# st-link.net
KiCad netlist of a schematic drawn in Altium Designer
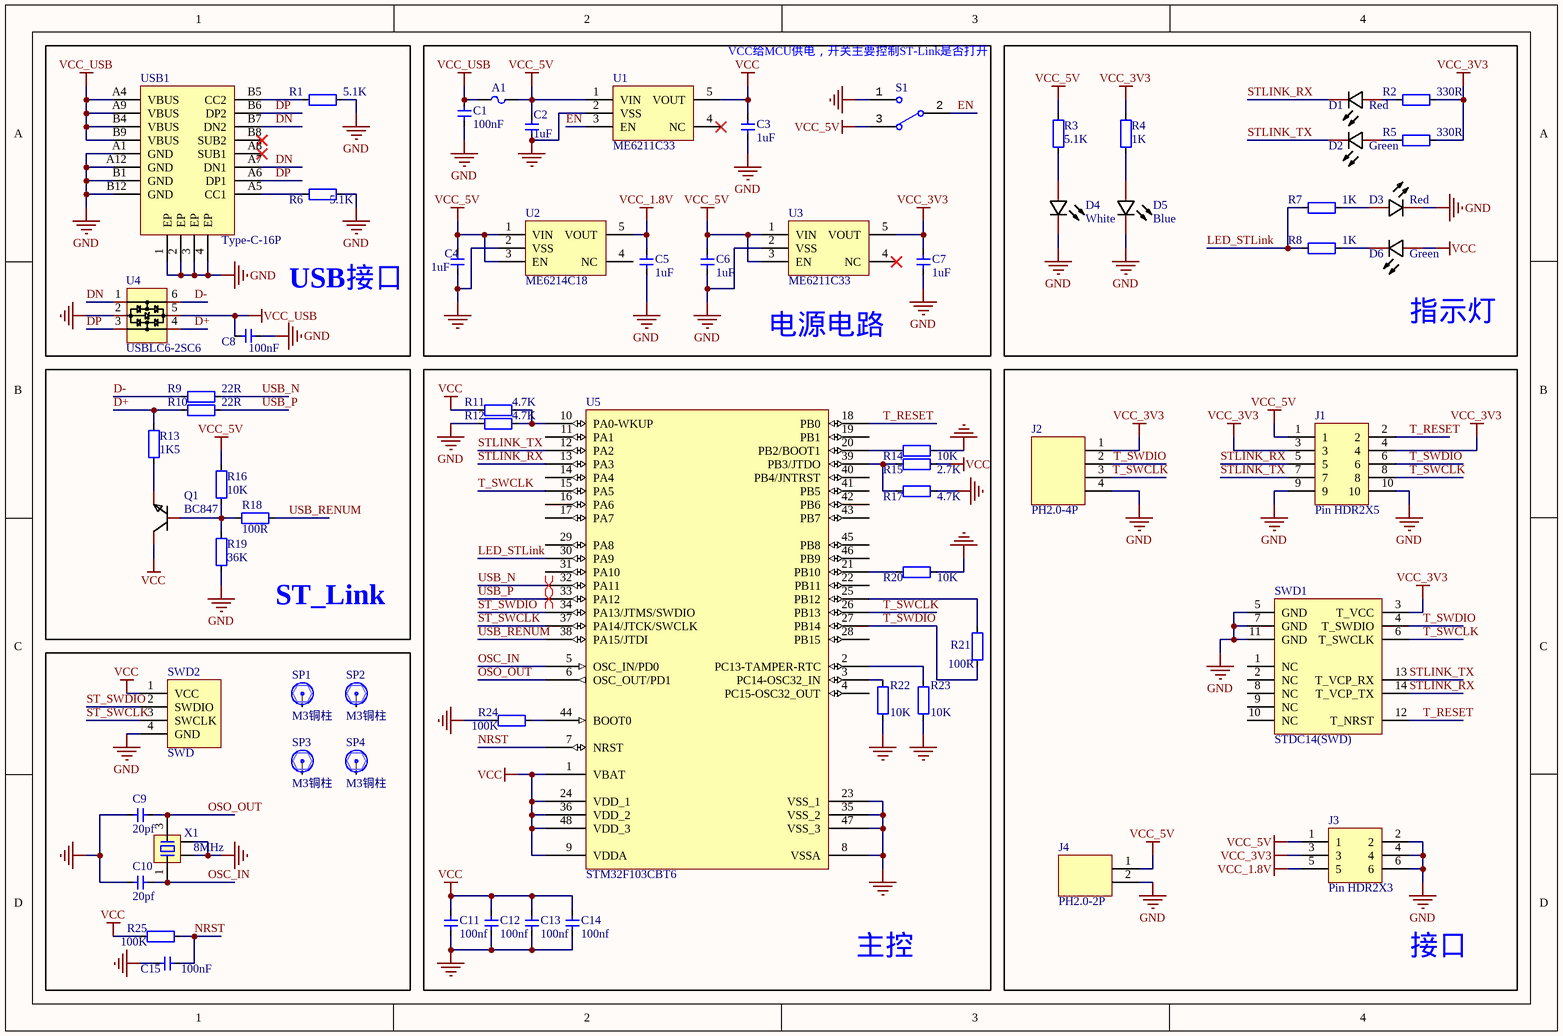
[diagram p0: st-link.SchDoc]

(export (version "E")
  (design (tool "Eeschema 10.0.6"))
  (components
    (comp (ref "A1")
      (value "ASMD1812-300")
      (footprint "FUSE-1812")
      (libsource (lib "xiaomo") (part "ASMD1812-300"))
    )
    (comp (ref "C1")
      (value "100nF")
      (footprint "CAP_0402")
      (description "Capacitor")
      (libsource (lib "xiaomo") (part "电容-0402"))
    )
    (comp (ref "C2")
      (value "1uF")
      (footprint "CAP_0402")
      (description "Capacitor")
      (libsource (lib "xiaomo") (part "电容-0402"))
    )
    (comp (ref "C3")
      (value "1uF")
      (footprint "CAP_0402")
      (description "Capacitor")
      (libsource (lib "xiaomo") (part "电容-0402"))
    )
    (comp (ref "C4")
      (value "1uF")
      (footprint "CAP_0402")
      (description "Capacitor")
      (libsource (lib "xiaomo") (part "电容-0402"))
    )
    (comp (ref "C5")
      (value "1uF")
      (footprint "CAP_0402")
      (description "Capacitor")
      (libsource (lib "xiaomo") (part "电容-0402"))
    )
    (comp (ref "C6")
      (value "1uF")
      (footprint "CAP_0402")
      (description "Capacitor")
      (libsource (lib "xiaomo") (part "电容-0402"))
    )
    (comp (ref "C7")
      (value "1uF")
      (footprint "CAP_0402")
      (description "Capacitor")
      (libsource (lib "xiaomo") (part "电容-0402"))
    )
    (comp (ref "C8")
      (value "100nF")
      (footprint "CAP_0402")
      (description "Capacitor")
      (libsource (lib "xiaomo") (part "电容-0402"))
    )
    (comp (ref "C9")
      (value "20pf")
      (footprint "CAP_0402")
      (description "Capacitor")
      (libsource (lib "xiaomo") (part "电容-0402"))
    )
    (comp (ref "C10")
      (value "20pf")
      (footprint "CAP_0402")
      (description "Capacitor")
      (libsource (lib "xiaomo") (part "电容-0402"))
    )
    (comp (ref "C11")
      (value "100nf")
      (footprint "CAP_0402")
      (description "Capacitor")
      (libsource (lib "xiaomo") (part "电容-0402"))
    )
    (comp (ref "C12")
      (value "100nf")
      (footprint "CAP_0402")
      (description "Capacitor")
      (libsource (lib "xiaomo") (part "电容-0402"))
    )
    (comp (ref "C13")
      (value "100nf")
      (footprint "CAP_0402")
      (description "Capacitor")
      (libsource (lib "xiaomo") (part "电容-0402"))
    )
    (comp (ref "C14")
      (value "100nf")
      (footprint "CAP_0402")
      (description "Capacitor")
      (libsource (lib "xiaomo") (part "电容-0402"))
    )
    (comp (ref "C15")
      (value "100nF")
      (footprint "CAP_0402")
      (description "Capacitor")
      (libsource (lib "xiaomo") (part "电容-0402"))
    )
    (comp (ref "D1")
      (value "Red")
      (footprint "LED-0603G")
      (description "0603LED")
      (libsource (lib "xiaomo") (part "LED0603"))
    )
    (comp (ref "D2")
      (value "Green")
      (footprint "LED-0603G")
      (description "0603LED")
      (libsource (lib "xiaomo") (part "LED0603"))
    )
    (comp (ref "D3")
      (value "Red")
      (footprint "LED-0603G")
      (description "0603LED")
      (libsource (lib "xiaomo") (part "LED0603"))
    )
    (comp (ref "D4")
      (value "White")
      (footprint "LED-0603G")
      (description "0603LED")
      (libsource (lib "xiaomo") (part "LED0603"))
    )
    (comp (ref "D5")
      (value "Blue")
      (footprint "LED-0603G")
      (description "0603LED")
      (libsource (lib "xiaomo") (part "LED0603"))
    )
    (comp (ref "D6")
      (value "Green")
      (footprint "LED-0603G")
      (description "0603LED")
      (libsource (lib "xiaomo") (part "LED0603"))
    )
    (comp (ref "J1")
      (value "Pin HDR2X5")
      (footprint "Pin HDR2X5/2.54mm-S")
      (libsource (lib "排针") (part "Pin HDR2X5"))
    )
    (comp (ref "J2") (value "PH2.0-4P") (footprint "PH2.0-4P") (libsource (lib "PH") (part "PH2.0-4P")))
    (comp (ref "J3")
      (value "Pin HDR2X3")
      (footprint "Pin HDR2X3/2.54mm-S")
      (libsource (lib "排针") (part "Pin HDR2X3"))
    )
    (comp (ref "J4") (value "PH2.0-2P") (footprint "PH2.0-2P") (libsource (lib "PH") (part "PH2.0-2P")))
    (comp (ref "Q1") (value "BC847") (footprint "SOT23-3") (libsource (lib "xiaomo") (part "NPN")))
    (comp (ref "R1")
      (value "5.1K")
      (footprint "RES_0402")
      (description "Resistor")
      (libsource (lib "") (part "电阻-0402_2"))
    )
    (comp (ref "R2")
      (value "330R")
      (footprint "RES_0402")
      (description "Resistor")
      (libsource (lib "") (part "电阻-0402_2"))
    )
    (comp (ref "R3")
      (value "5.1K")
      (footprint "RES_0402")
      (description "Resistor")
      (libsource (lib "") (part "电阻-0402_1"))
    )
    (comp (ref "R4")
      (value "1K")
      (footprint "RES_0402")
      (description "Resistor")
      (libsource (lib "") (part "电阻-0402_1"))
    )
    (comp (ref "R5")
      (value "330R")
      (footprint "RES_0402")
      (description "Resistor")
      (libsource (lib "") (part "电阻-0402_2"))
    )
    (comp (ref "R6")
      (value "5.1K")
      (footprint "RES_0402")
      (description "Resistor")
      (libsource (lib "") (part "电阻-0402_2"))
    )
    (comp (ref "R7")
      (value "1K")
      (footprint "RES_0402")
      (description "Resistor")
      (libsource (lib "") (part "电阻-0402_2"))
    )
    (comp (ref "R8")
      (value "1K")
      (footprint "RES_0402")
      (description "Resistor")
      (libsource (lib "") (part "电阻-0402_2"))
    )
    (comp (ref "R9")
      (value "22R")
      (footprint "RES_0402")
      (description "Resistor")
      (libsource (lib "") (part "电阻-0402_2"))
    )
    (comp (ref "R10")
      (value "22R")
      (footprint "RES_0402")
      (description "Resistor")
      (libsource (lib "") (part "电阻-0402_2"))
    )
    (comp (ref "R11")
      (value "4.7K")
      (footprint "RES_0402")
      (description "Resistor")
      (libsource (lib "") (part "电阻-0402_3"))
    )
    (comp (ref "R12")
      (value "4.7K")
      (footprint "RES_0402")
      (description "Resistor")
      (libsource (lib "") (part "电阻-0402_3"))
    )
    (comp (ref "R13")
      (value "1K5")
      (footprint "RES_0402")
      (description "Resistor")
      (libsource (lib "xiaomo") (part "电阻-0402"))
    )
    (comp (ref "R14")
      (value "10K")
      (footprint "RES_0402")
      (description "Resistor")
      (libsource (lib "") (part "电阻-0402_2"))
    )
    (comp (ref "R15")
      (value "2.7K")
      (footprint "RES_0402")
      (description "Resistor")
      (libsource (lib "") (part "电阻-0402_2"))
    )
    (comp (ref "R16")
      (value "10K")
      (footprint "RES_0402")
      (description "Resistor")
      (libsource (lib "xiaomo") (part "电阻-0402"))
    )
    (comp (ref "R17")
      (value "4.7K")
      (footprint "RES_0402")
      (description "Resistor")
      (libsource (lib "") (part "电阻-0402_2"))
    )
    (comp (ref "R18")
      (value "100R")
      (footprint "RES_0402")
      (description "Resistor")
      (libsource (lib "") (part "电阻-0402_2"))
    )
    (comp (ref "R19")
      (value "36K")
      (footprint "RES_0402")
      (description "Resistor")
      (libsource (lib "xiaomo") (part "电阻-0402"))
    )
    (comp (ref "R20")
      (value "10K")
      (footprint "RES_0402")
      (description "Resistor")
      (libsource (lib "") (part "电阻-0402_2"))
    )
    (comp (ref "R21")
      (value "100R")
      (footprint "RES_0402")
      (description "Resistor")
      (libsource (lib "") (part "电阻-0402_1"))
    )
    (comp (ref "R22")
      (value "10K")
      (footprint "RES_0402")
      (description "Resistor")
      (libsource (lib "") (part "电阻-0402_1"))
    )
    (comp (ref "R23")
      (value "10K")
      (footprint "RES_0402")
      (description "Resistor")
      (libsource (lib "") (part "电阻-0402_1"))
    )
    (comp (ref "R24")
      (value "100K")
      (footprint "RES_0402")
      (description "Resistor")
      (libsource (lib "") (part "电阻-0402_3"))
    )
    (comp (ref "R25")
      (value "100K")
      (footprint "RES_0402")
      (description "Resistor")
      (libsource (lib "") (part "电阻-0402_3"))
    )
    (comp (ref "S1")
      (value "SPDT 3P")
      (footprint "SwitchSPDT_2.8X6.6_90")
      (description "Switch")
      (libsource (lib "xiaomo") (part "SwitchSPDT_2.8x6.6_90"))
    )
    (comp (ref "SP1")
      (value "M3铜柱")
      (footprint "铜柱")
      (description "铜柱")
      (fields (field (name "版权归属") "源创客"))
      (libsource (lib "固定柱") (part "铜柱"))
    )
    (comp (ref "SP2")
      (value "M3铜柱")
      (footprint "铜柱")
      (description "铜柱")
      (fields (field (name "版权归属") "源创客"))
      (libsource (lib "固定柱") (part "铜柱"))
    )
    (comp (ref "SP3")
      (value "M3铜柱")
      (footprint "铜柱")
      (description "铜柱")
      (fields (field (name "版权归属") "源创客"))
      (libsource (lib "固定柱") (part "铜柱"))
    )
    (comp (ref "SP4")
      (value "M3铜柱")
      (footprint "铜柱")
      (description "铜柱")
      (fields (field (name "版权归属") "源创客"))
      (libsource (lib "固定柱") (part "铜柱"))
    )
    (comp (ref "SWD1")
      (value "STDC14(SWD)")
      (footprint "STDC14")
      (description "For STLINK_V3SET")
      (libsource (lib "xiaomo") (part "STDC14(SWD)"))
    )
    (comp (ref "SWD2") (value "SWD") (footprint "焊点×4") (libsource (lib "xiaomo") (part "SWD")))
    (comp (ref "U1")
      (value "ME6211C33")
      (footprint "SOT23-5")
      (description "低压差线性稳压器")
      (libsource (lib "xiaomo") (part "ME6211C"))
    )
    (comp (ref "U2")
      (value "ME6214C18")
      (footprint "SOT23-5")
      (description "低压差线性稳压器")
      (libsource (lib "xiaomo") (part "ME6211C"))
    )
    (comp (ref "U3")
      (value "ME6211C33")
      (footprint "SOT23-5")
      (description "低压差线性稳压器")
      (libsource (lib "xiaomo") (part "ME6211C"))
    )
    (comp (ref "U4")
      (value "USBLC6-2SC6")
      (footprint "SOT23-6")
      (description "静电放电(ESD)保护器件，反向截止电压(Vrwm)：5.25V 击穿电压：6V 峰值脉冲电流(Ipp)：5A@8/20us 最大钳位电压(Vc)@Ipp：17V")
      (libsource (lib "xiaomo") (part "USBLC6-2SC6"))
    )
    (comp (ref "U5")
      (value "STM32F103CBT6")
      (footprint "LQFP48 7X7")
      (libsource (lib "STM32系列") (part "STM32F103C8T6"))
    )
    (comp (ref "USB1")
      (value "Type-C-16P")
      (footprint "USB-C-SMD_KH-TYPE-C-16P")
      (description "C709357")
      (libsource (lib "xiaomo") (part "Type-C-16P"))
    )
    (comp (ref "X1")
      (value "8MHz")
      (footprint "OSC 3225-4P")
      (description "4脚无源晶振")
      (libsource (lib "晶振") (part "XTAL-4P"))
    )
  )
  (nets
    (net (code "1") (name "/D+") (class "Default")
      (node (ref "R10") (pin "1") (pinfunction "1_1") (pintype "passive"))
      (node (ref "R13") (pin "2") (pinfunction "2_2") (pintype "passive"))
      (node (ref "U4") (pin "4") (pinfunction "I/O2_4") (pintype "passive"))
    )
    (net (code "2") (name "/D-") (class "Default")
      (node (ref "R9") (pin "1") (pinfunction "1_1") (pintype "passive"))
      (node (ref "U4") (pin "6") (pinfunction "I/O1_6") (pintype "passive"))
    )
    (net (code "3") (name "/DN") (class "Default")
      (node (ref "U4") (pin "1") (pinfunction "I/O1_1") (pintype "passive"))
      (node (ref "USB1") (pin "A7") (pinfunction "DN1_A7") (pintype "passive"))
      (node (ref "USB1") (pin "B7") (pinfunction "DN2_B7") (pintype "passive"))
    )
    (net (code "4") (name "/DP") (class "Default")
      (node (ref "U4") (pin "3") (pinfunction "I/O2_3") (pintype "passive"))
      (node (ref "USB1") (pin "A6") (pinfunction "DP1_A6") (pintype "passive"))
      (node (ref "USB1") (pin "B6") (pinfunction "DP2_B6") (pintype "passive"))
    )
    (net (code "5") (name "/EN") (class "Default")
      (node (ref "S1") (pin "2") (pinfunction "2_2") (pintype "passive"))
      (node (ref "U1") (pin "3") (pinfunction "EN_3") (pintype "passive"))
    )
    (net (code "6") (name "/LED_STLink") (class "Default")
      (node (ref "R7") (pin "1") (pinfunction "1_1") (pintype "passive"))
      (node (ref "R8") (pin "1") (pinfunction "1_1") (pintype "passive"))
      (node (ref "U5") (pin "30") (pinfunction "PA9_30") (pintype "bidirectional"))
    )
    (net (code "7") (name "/NRST") (class "Default")
      (node (ref "C15") (pin "2") (pinfunction "2_2") (pintype "passive"))
      (node (ref "R25") (pin "1") (pinfunction "1_1") (pintype "passive"))
      (node (ref "U5") (pin "7") (pinfunction "NRST_7") (pintype "bidirectional"))
    )
    (net (code "8") (name "/OSC_IN") (class "Default")
      (node (ref "C10") (pin "2") (pinfunction "2_2") (pintype "passive"))
      (node (ref "U5") (pin "5") (pinfunction "OSC_IN/PD0_5") (pintype "input"))
      (node (ref "X1") (pin "1") (pinfunction "1_1") (pintype "passive"))
    )
    (net (code "9") (name "/OSO_OUT") (class "Default")
      (node (ref "C9") (pin "2") (pinfunction "2_2") (pintype "passive"))
      (node (ref "U5") (pin "6") (pinfunction "OSC_OUT/PD1_6") (pintype "output"))
      (node (ref "X1") (pin "3") (pinfunction "3_3") (pintype "passive"))
    )
    (net (code "10") (name "/STLINK_RX") (class "Default")
      (node (ref "D1") (pin "K") (pinfunction "C_K") (pintype "passive"))
      (node (ref "J1") (pin "5") (pinfunction "5_5") (pintype "passive"))
      (node (ref "SWD1") (pin "14") (pinfunction "T_VCP_TX_14") (pintype "passive"))
      (node (ref "U5") (pin "13") (pinfunction "PA3_13") (pintype "bidirectional"))
    )
    (net (code "11") (name "/STLINK_TX") (class "Default")
      (node (ref "D2") (pin "K") (pinfunction "C_K") (pintype "passive"))
      (node (ref "J1") (pin "7") (pinfunction "7_7") (pintype "passive"))
      (node (ref "SWD1") (pin "13") (pinfunction "T_VCP_RX_13") (pintype "passive"))
      (node (ref "U5") (pin "12") (pinfunction "PA2_12") (pintype "bidirectional"))
    )
    (net (code "12") (name "/ST_SWCLK") (class "Default")
      (node (ref "SWD2") (pin "3") (pinfunction "SWCLK_3") (pintype "passive"))
      (node (ref "U5") (pin "37") (pinfunction "PA14/JTCK/SWCLK_37") (pintype "bidirectional"))
    )
    (net (code "13") (name "/ST_SWDIO") (class "Default")
      (node (ref "SWD2") (pin "2") (pinfunction "SWDIO_2") (pintype "passive"))
      (node (ref "U5") (pin "34") (pinfunction "PA13/JTMS/SWDIO_34") (pintype "bidirectional"))
    )
    (net (code "14") (name "/T_RESET") (class "Default")
      (node (ref "J1") (pin "2") (pinfunction "2_2") (pintype "passive"))
      (node (ref "SWD1") (pin "12") (pinfunction "T_NRST_12") (pintype "passive"))
      (node (ref "U5") (pin "18") (pinfunction "PB0_18") (pintype "bidirectional"))
    )
    (net (code "15") (name "/T_SWCLK") (class "Default")
      (node (ref "J1") (pin "8") (pinfunction "8_8") (pintype "passive"))
      (node (ref "J2") (pin "3") (pinfunction "3_3") (pintype "passive"))
      (node (ref "SWD1") (pin "6") (pinfunction "T_SWCLK_6") (pintype "passive"))
      (node (ref "U5") (pin "15") (pinfunction "PA5_15") (pintype "bidirectional"))
      (node (ref "U5") (pin "26") (pinfunction "PB13_26") (pintype "bidirectional"))
    )
    (net (code "16") (name "/T_SWDIO") (class "Default")
      (node (ref "J1") (pin "6") (pinfunction "6_6") (pintype "passive"))
      (node (ref "J2") (pin "2") (pinfunction "2_2") (pintype "passive"))
      (node (ref "R21") (pin "2") (pinfunction "2_2") (pintype "passive"))
      (node (ref "SWD1") (pin "4") (pinfunction "T_SWDIO_4") (pintype "passive"))
      (node (ref "U5") (pin "27") (pinfunction "PB14_27") (pintype "bidirectional"))
    )
    (net (code "17") (name "/USB_N") (class "Default")
      (node (ref "R9") (pin "2") (pinfunction "2_2") (pintype "passive"))
      (node (ref "U5") (pin "32") (pinfunction "PA11_32") (pintype "bidirectional"))
    )
    (net (code "18") (name "/USB_P") (class "Default")
      (node (ref "R10") (pin "2") (pinfunction "2_2") (pintype "passive"))
      (node (ref "U5") (pin "33") (pinfunction "PA12_33") (pintype "bidirectional"))
    )
    (net (code "19") (name "/USB_RENUM") (class "Default")
      (node (ref "R18") (pin "2") (pinfunction "2_2") (pintype "passive"))
      (node (ref "U5") (pin "38") (pinfunction "PA15/JTDI_38") (pintype "bidirectional"))
    )
    (net (code "20") (name "GND") (class "Default")
      (node (ref "C1") (pin "2") (pinfunction "2_2") (pintype "passive"))
      (node (ref "C10") (pin "1") (pinfunction "1_1") (pintype "passive"))
      (node (ref "C11") (pin "1") (pinfunction "1_1") (pintype "passive"))
      (node (ref "C12") (pin "1") (pinfunction "1_1") (pintype "passive"))
      (node (ref "C13") (pin "1") (pinfunction "1_1") (pintype "passive"))
      (node (ref "C14") (pin "1") (pinfunction "1_1") (pintype "passive"))
      (node (ref "C15") (pin "1") (pinfunction "1_1") (pintype "passive"))
      (node (ref "C2") (pin "2") (pinfunction "2_2") (pintype "passive"))
      (node (ref "C3") (pin "2") (pinfunction "2_2") (pintype "passive"))
      (node (ref "C4") (pin "2") (pinfunction "2_2") (pintype "passive"))
      (node (ref "C5") (pin "2") (pinfunction "2_2") (pintype "passive"))
      (node (ref "C6") (pin "2") (pinfunction "2_2") (pintype "passive"))
      (node (ref "C7") (pin "2") (pinfunction "2_2") (pintype "passive"))
      (node (ref "C8") (pin "2") (pinfunction "2_2") (pintype "passive"))
      (node (ref "C9") (pin "1") (pinfunction "1_1") (pintype "passive"))
      (node (ref "D3") (pin "K") (pinfunction "C_K") (pintype "passive"))
      (node (ref "D4") (pin "K") (pinfunction "C_K") (pintype "passive"))
      (node (ref "D5") (pin "K") (pinfunction "C_K") (pintype "passive"))
      (node (ref "J1") (pin "10") (pinfunction "10_10") (pintype "passive"))
      (node (ref "J1") (pin "9") (pinfunction "9_9") (pintype "passive"))
      (node (ref "J2") (pin "4") (pinfunction "4_4") (pintype "passive"))
      (node (ref "J3") (pin "2") (pinfunction "2_2") (pintype "passive"))
      (node (ref "J3") (pin "4") (pinfunction "4_4") (pintype "passive"))
      (node (ref "J3") (pin "6") (pinfunction "6_6") (pintype "passive"))
      (node (ref "J4") (pin "2") (pinfunction "2_2") (pintype "passive"))
      (node (ref "R1") (pin "2") (pinfunction "2_2") (pintype "passive"))
      (node (ref "R12") (pin "2") (pinfunction "2_2") (pintype "passive"))
      (node (ref "R14") (pin "2") (pinfunction "2_2") (pintype "passive"))
      (node (ref "R17") (pin "2") (pinfunction "2_2") (pintype "passive"))
      (node (ref "R19") (pin "1") (pinfunction "1_1") (pintype "passive"))
      (node (ref "R20") (pin "2") (pinfunction "2_2") (pintype "passive"))
      (node (ref "R22") (pin "2") (pinfunction "2_2") (pintype "passive"))
      (node (ref "R23") (pin "2") (pinfunction "2_2") (pintype "passive"))
      (node (ref "R24") (pin "2") (pinfunction "2_2") (pintype "passive"))
      (node (ref "R6") (pin "2") (pinfunction "2_2") (pintype "passive"))
      (node (ref "S1") (pin "1") (pinfunction "1_1") (pintype "passive"))
      (node (ref "SWD1") (pin "11") (pinfunction "GND_11") (pintype "passive"))
      (node (ref "SWD1") (pin "5") (pinfunction "GND_5") (pintype "passive"))
      (node (ref "SWD1") (pin "7") (pinfunction "GND_7") (pintype "passive"))
      (node (ref "SWD2") (pin "4") (pinfunction "GND_4") (pintype "passive"))
      (node (ref "U1") (pin "2") (pinfunction "VSS_2") (pintype "passive"))
      (node (ref "U2") (pin "2") (pinfunction "VSS_2") (pintype "passive"))
      (node (ref "U3") (pin "2") (pinfunction "VSS_2") (pintype "passive"))
      (node (ref "U4") (pin "2") (pinfunction "GND_2") (pintype "passive"))
      (node (ref "U5") (pin "23") (pinfunction "VSS_1_23") (pintype "power_in"))
      (node (ref "U5") (pin "35") (pinfunction "VSS_2_35") (pintype "power_in"))
      (node (ref "U5") (pin "47") (pinfunction "VSS_3_47") (pintype "power_in"))
      (node (ref "U5") (pin "8") (pinfunction "VSSA_8") (pintype "power_in"))
      (node (ref "USB1") (pin "1") (pinfunction "EP_1") (pintype "passive"))
      (node (ref "USB1") (pin "2") (pinfunction "EP_2") (pintype "passive"))
      (node (ref "USB1") (pin "3") (pinfunction "EP_3") (pintype "passive"))
      (node (ref "USB1") (pin "4") (pinfunction "EP_4") (pintype "passive"))
      (node (ref "USB1") (pin "A1") (pinfunction "GND_A1") (pintype "passive"))
      (node (ref "USB1") (pin "A12") (pinfunction "GND_A12") (pintype "passive"))
      (node (ref "USB1") (pin "B1") (pinfunction "GND_B1") (pintype "passive"))
      (node (ref "USB1") (pin "B12") (pinfunction "GND_B12") (pintype "passive"))
      (node (ref "X1") (pin "2") (pinfunction "2_2") (pintype "passive"))
      (node (ref "X1") (pin "4") (pinfunction "4_4") (pintype "passive"))
    )
    (net (code "21") (name "Net-(D1-PadA)") (class "Default")
      (node (ref "D1") (pin "A") (pinfunction "A_A") (pintype "passive"))
      (node (ref "R2") (pin "1") (pinfunction "1_1") (pintype "passive"))
    )
    (net (code "22") (name "Net-(D2-PadA)") (class "Default")
      (node (ref "D2") (pin "A") (pinfunction "A_A") (pintype "passive"))
      (node (ref "R5") (pin "1") (pinfunction "1_1") (pintype "passive"))
    )
    (net (code "23") (name "Net-(D3-PadA)") (class "Default")
      (node (ref "D3") (pin "A") (pinfunction "A_A") (pintype "passive"))
      (node (ref "R7") (pin "2") (pinfunction "2_2") (pintype "passive"))
    )
    (net (code "24") (name "Net-(D4-PadA)") (class "Default")
      (node (ref "D4") (pin "A") (pinfunction "A_A") (pintype "passive"))
      (node (ref "R3") (pin "2") (pinfunction "2_2") (pintype "passive"))
    )
    (net (code "25") (name "Net-(D5-PadA)") (class "Default")
      (node (ref "D5") (pin "A") (pinfunction "A_A") (pintype "passive"))
      (node (ref "R4") (pin "2") (pinfunction "2_2") (pintype "passive"))
    )
    (net (code "26") (name "Net-(D6-C)") (class "Default")
      (node (ref "D6") (pin "K") (pinfunction "C_K") (pintype "passive"))
      (node (ref "R8") (pin "2") (pinfunction "2_2") (pintype "passive"))
    )
    (net (code "27") (name "Net-(Q1-B)") (class "Default")
      (node (ref "Q1") (pin "1") (pinfunction "B_1") (pintype "passive"))
      (node (ref "R16") (pin "1") (pinfunction "1_1") (pintype "passive"))
      (node (ref "R18") (pin "1") (pinfunction "1_1") (pintype "passive"))
      (node (ref "R19") (pin "2") (pinfunction "2_2") (pintype "passive"))
    )
    (net (code "28") (name "Net-(Q1-E)") (class "Default")
      (node (ref "Q1") (pin "2") (pinfunction "E_2") (pintype "passive"))
      (node (ref "R13") (pin "1") (pinfunction "1_1") (pintype "passive"))
    )
    (net (code "29") (name "Net-(U5-BOOT0)") (class "Default")
      (node (ref "R24") (pin "1") (pinfunction "1_1") (pintype "passive"))
      (node (ref "U5") (pin "44") (pinfunction "BOOT0_44") (pintype "input"))
    )
    (net (code "30") (name "Net-(U5-PA0-WKUP)") (class "Default")
      (node (ref "R11") (pin "1") (pinfunction "1_1") (pintype "passive"))
      (node (ref "R12") (pin "1") (pinfunction "1_1") (pintype "passive"))
      (node (ref "U5") (pin "10") (pinfunction "PA0-WKUP_10") (pintype "bidirectional"))
    )
    (net (code "31") (name "Net-(U5-PB2{slash}BOOT1)") (class "Default")
      (node (ref "R14") (pin "1") (pinfunction "1_1") (pintype "passive"))
      (node (ref "U5") (pin "20") (pinfunction "PB2/BOOT1_20") (pintype "bidirectional"))
    )
    (net (code "32") (name "Net-(U5-PB3{slash}JTDO)") (class "Default")
      (node (ref "R15") (pin "1") (pinfunction "1_1") (pintype "passive"))
      (node (ref "R17") (pin "1") (pinfunction "1_1") (pintype "passive"))
      (node (ref "U5") (pin "39") (pinfunction "PB3/JTDO_39") (pintype "bidirectional"))
    )
    (net (code "33") (name "Net-(U5-PB10)") (class "Default")
      (node (ref "R20") (pin "1") (pinfunction "1_1") (pintype "passive"))
      (node (ref "U5") (pin "21") (pinfunction "PB10_21") (pintype "bidirectional"))
    )
    (net (code "34") (name "Net-(U5-PB12)") (class "Default")
      (node (ref "R21") (pin "1") (pinfunction "1_1") (pintype "passive"))
      (node (ref "U5") (pin "25") (pinfunction "PB12_25") (pintype "bidirectional"))
    )
    (net (code "35") (name "Net-(U5-PC13-TAMPER-RTC)") (class "Default")
      (node (ref "R23") (pin "1") (pinfunction "1_1") (pintype "passive"))
      (node (ref "U5") (pin "2") (pinfunction "PC13-TAMPER-RTC_2") (pintype "bidirectional"))
    )
    (net (code "36") (name "Net-(U5-PC14-OSC32_IN)") (class "Default")
      (node (ref "R22") (pin "1") (pinfunction "1_1") (pintype "passive"))
      (node (ref "U5") (pin "3") (pinfunction "PC14-OSC32_IN_3") (pintype "bidirectional"))
    )
    (net (code "37") (name "Net-(USB1-CC1)") (class "Default")
      (node (ref "R6") (pin "1") (pinfunction "1_1") (pintype "passive"))
      (node (ref "USB1") (pin "A5") (pinfunction "CC1_A5") (pintype "passive"))
    )
    (net (code "38") (name "Net-(USB1-CC2)") (class "Default")
      (node (ref "R1") (pin "1") (pinfunction "1_1") (pintype "passive"))
      (node (ref "USB1") (pin "B5") (pinfunction "CC2_B5") (pintype "passive"))
    )
    (net (code "39") (name "VCC") (class "Default")
      (node (ref "C11") (pin "2") (pinfunction "2_2") (pintype "passive"))
      (node (ref "C12") (pin "2") (pinfunction "2_2") (pintype "passive"))
      (node (ref "C13") (pin "2") (pinfunction "2_2") (pintype "passive"))
      (node (ref "C14") (pin "2") (pinfunction "2_2") (pintype "passive"))
      (node (ref "C3") (pin "1") (pinfunction "1_1") (pintype "passive"))
      (node (ref "D6") (pin "A") (pinfunction "A_A") (pintype "passive"))
      (node (ref "Q1") (pin "3") (pinfunction "C_3") (pintype "passive"))
      (node (ref "R11") (pin "2") (pinfunction "2_2") (pintype "passive"))
      (node (ref "R15") (pin "2") (pinfunction "2_2") (pintype "passive"))
      (node (ref "R25") (pin "2") (pinfunction "2_2") (pintype "passive"))
      (node (ref "SWD2") (pin "1") (pinfunction "VCC_1") (pintype "passive"))
      (node (ref "U1") (pin "5") (pinfunction "VOUT_5") (pintype "passive"))
      (node (ref "U5") (pin "1") (pinfunction "VBAT_1") (pintype "power_in"))
      (node (ref "U5") (pin "24") (pinfunction "VDD_1_24") (pintype "power_in"))
      (node (ref "U5") (pin "36") (pinfunction "VDD_2_36") (pintype "power_in"))
      (node (ref "U5") (pin "48") (pinfunction "VDD_3_48") (pintype "power_in"))
      (node (ref "U5") (pin "9") (pinfunction "VDDA_9") (pintype "power_in"))
    )
    (net (code "40") (name "VCC_1.8V") (class "Default")
      (node (ref "C5") (pin "1") (pinfunction "1_1") (pintype "passive"))
      (node (ref "J3") (pin "5") (pinfunction "5_5") (pintype "passive"))
      (node (ref "U2") (pin "5") (pinfunction "VOUT_5") (pintype "passive"))
    )
    (net (code "41") (name "VCC_3V3") (class "Default")
      (node (ref "C7") (pin "1") (pinfunction "1_1") (pintype "passive"))
      (node (ref "J1") (pin "3") (pinfunction "3_3") (pintype "passive"))
      (node (ref "J1") (pin "4") (pinfunction "4_4") (pintype "passive"))
      (node (ref "J2") (pin "1") (pinfunction "1_1") (pintype "passive"))
      (node (ref "J3") (pin "3") (pinfunction "3_3") (pintype "passive"))
      (node (ref "R2") (pin "2") (pinfunction "2_2") (pintype "passive"))
      (node (ref "R4") (pin "1") (pinfunction "1_1") (pintype "passive"))
      (node (ref "R5") (pin "2") (pinfunction "2_2") (pintype "passive"))
      (node (ref "SWD1") (pin "3") (pinfunction "T_VCC_3") (pintype "passive"))
      (node (ref "U3") (pin "5") (pinfunction "VOUT_5") (pintype "passive"))
    )
    (net (code "42") (name "VCC_5V") (class "Default")
      (node (ref "A1") (pin "2") (pinfunction "2_2") (pintype "passive"))
      (node (ref "C2") (pin "1") (pinfunction "1_1") (pintype "passive"))
      (node (ref "C4") (pin "1") (pinfunction "1_1") (pintype "passive"))
      (node (ref "C6") (pin "1") (pinfunction "1_1") (pintype "passive"))
      (node (ref "J1") (pin "1") (pinfunction "1_1") (pintype "passive"))
      (node (ref "J3") (pin "1") (pinfunction "1_1") (pintype "passive"))
      (node (ref "J4") (pin "1") (pinfunction "1_1") (pintype "passive"))
      (node (ref "R16") (pin "2") (pinfunction "2_2") (pintype "passive"))
      (node (ref "R3") (pin "1") (pinfunction "1_1") (pintype "passive"))
      (node (ref "S1") (pin "3") (pinfunction "3_3") (pintype "passive"))
      (node (ref "U1") (pin "1") (pinfunction "VIN_1") (pintype "passive"))
      (node (ref "U2") (pin "1") (pinfunction "VIN_1") (pintype "passive"))
      (node (ref "U2") (pin "3") (pinfunction "EN_3") (pintype "passive"))
      (node (ref "U3") (pin "1") (pinfunction "VIN_1") (pintype "passive"))
      (node (ref "U3") (pin "3") (pinfunction "EN_3") (pintype "passive"))
    )
    (net (code "43") (name "VCC_USB") (class "Default")
      (node (ref "A1") (pin "1") (pinfunction "1_1") (pintype "passive"))
      (node (ref "C1") (pin "1") (pinfunction "1_1") (pintype "passive"))
      (node (ref "C8") (pin "1") (pinfunction "1_1") (pintype "passive"))
      (node (ref "U4") (pin "5") (pinfunction "VBUS_5") (pintype "passive"))
      (node (ref "USB1") (pin "A4") (pinfunction "VBUS_A4") (pintype "passive"))
      (node (ref "USB1") (pin "A9") (pinfunction "VBUS_A9") (pintype "passive"))
      (node (ref "USB1") (pin "B4") (pinfunction "VBUS_B4") (pintype "passive"))
      (node (ref "USB1") (pin "B9") (pinfunction "VBUS_B9") (pintype "passive"))
    )
    (net (code "44") (name "unconnected-(SP1-Pad1)") (class "Default")
      (node (ref "SP1") (pin "1") (pinfunction "1_1") (pintype "passive"))
    )
    (net (code "45") (name "unconnected-(SP2-Pad1)") (class "Default")
      (node (ref "SP2") (pin "1") (pinfunction "1_1") (pintype "passive"))
    )
    (net (code "46") (name "unconnected-(SP3-Pad1)") (class "Default")
      (node (ref "SP3") (pin "1") (pinfunction "1_1") (pintype "passive"))
    )
    (net (code "47") (name "unconnected-(SP4-Pad1)") (class "Default")
      (node (ref "SP4") (pin "1") (pinfunction "1_1") (pintype "passive"))
    )
    (net (code "48") (name "unconnected-(SWD1-NC-Pad1)") (class "Default")
      (node (ref "SWD1") (pin "1") (pinfunction "NC_1") (pintype "passive"))
    )
    (net (code "49") (name "unconnected-(SWD1-NC-Pad2)") (class "Default")
      (node (ref "SWD1") (pin "2") (pinfunction "NC_2") (pintype "passive"))
    )
    (net (code "50") (name "unconnected-(SWD1-NC-Pad8)") (class "Default")
      (node (ref "SWD1") (pin "8") (pinfunction "NC_8") (pintype "passive"))
    )
    (net (code "51") (name "unconnected-(SWD1-NC-Pad9)") (class "Default")
      (node (ref "SWD1") (pin "9") (pinfunction "NC_9") (pintype "passive"))
    )
    (net (code "52") (name "unconnected-(SWD1-NC-Pad10)") (class "Default")
      (node (ref "SWD1") (pin "10") (pinfunction "NC_10") (pintype "passive"))
    )
    (net (code "53") (name "unconnected-(U1-NC-Pad4)") (class "Default")
      (node (ref "U1") (pin "4") (pinfunction "NC_4") (pintype "passive+no_connect"))
    )
    (net (code "54") (name "unconnected-(U2-NC-Pad4)") (class "Default")
      (node (ref "U2") (pin "4") (pinfunction "NC_4") (pintype "passive"))
    )
    (net (code "55") (name "unconnected-(U3-NC-Pad4)") (class "Default")
      (node (ref "U3") (pin "4") (pinfunction "NC_4") (pintype "passive+no_connect"))
    )
    (net (code "56") (name "unconnected-(U5-PA1-Pad11)") (class "Default")
      (node (ref "U5") (pin "11") (pinfunction "PA1_11") (pintype "bidirectional"))
    )
    (net (code "57") (name "unconnected-(U5-PA4-Pad14)") (class "Default")
      (node (ref "U5") (pin "14") (pinfunction "PA4_14") (pintype "bidirectional"))
    )
    (net (code "58") (name "unconnected-(U5-PA6-Pad16)") (class "Default")
      (node (ref "U5") (pin "16") (pinfunction "PA6_16") (pintype "bidirectional"))
    )
    (net (code "59") (name "unconnected-(U5-PA7-Pad17)") (class "Default")
      (node (ref "U5") (pin "17") (pinfunction "PA7_17") (pintype "bidirectional"))
    )
    (net (code "60") (name "unconnected-(U5-PA8-Pad29)") (class "Default")
      (node (ref "U5") (pin "29") (pinfunction "PA8_29") (pintype "bidirectional"))
    )
    (net (code "61") (name "unconnected-(U5-PA10-Pad31)") (class "Default")
      (node (ref "U5") (pin "31") (pinfunction "PA10_31") (pintype "bidirectional"))
    )
    (net (code "62") (name "unconnected-(U5-PB1-Pad19)") (class "Default")
      (node (ref "U5") (pin "19") (pinfunction "PB1_19") (pintype "bidirectional"))
    )
    (net (code "63") (name "unconnected-(U5-PB4{slash}JNTRST-Pad40)") (class "Default")
      (node (ref "U5") (pin "40") (pinfunction "PB4/JNTRST_40") (pintype "bidirectional"))
    )
    (net (code "64") (name "unconnected-(U5-PB5-Pad41)") (class "Default")
      (node (ref "U5") (pin "41") (pinfunction "PB5_41") (pintype "bidirectional"))
    )
    (net (code "65") (name "unconnected-(U5-PB6-Pad42)") (class "Default")
      (node (ref "U5") (pin "42") (pinfunction "PB6_42") (pintype "bidirectional"))
    )
    (net (code "66") (name "unconnected-(U5-PB7-Pad43)") (class "Default")
      (node (ref "U5") (pin "43") (pinfunction "PB7_43") (pintype "bidirectional"))
    )
    (net (code "67") (name "unconnected-(U5-PB8-Pad45)") (class "Default")
      (node (ref "U5") (pin "45") (pinfunction "PB8_45") (pintype "bidirectional"))
    )
    (net (code "68") (name "unconnected-(U5-PB9-Pad46)") (class "Default")
      (node (ref "U5") (pin "46") (pinfunction "PB9_46") (pintype "bidirectional"))
    )
    (net (code "69") (name "unconnected-(U5-PB11-Pad22)") (class "Default")
      (node (ref "U5") (pin "22") (pinfunction "PB11_22") (pintype "bidirectional"))
    )
    (net (code "70") (name "unconnected-(U5-PB15-Pad28)") (class "Default")
      (node (ref "U5") (pin "28") (pinfunction "PB15_28") (pintype "bidirectional"))
    )
    (net (code "71") (name "unconnected-(U5-PC15-OSC32_OUT-Pad4)") (class "Default")
      (node (ref "U5") (pin "4") (pinfunction "PC15-OSC32_OUT_4") (pintype "bidirectional"))
    )
    (net (code "72") (name "unconnected-(USB1-SUB1-PadA8)") (class "Default")
      (node (ref "USB1") (pin "A8") (pinfunction "SUB1_A8") (pintype "passive+no_connect"))
    )
    (net (code "73") (name "unconnected-(USB1-SUB2-PadB8)") (class "Default")
      (node (ref "USB1") (pin "B8") (pinfunction "SUB2_B8") (pintype "passive+no_connect"))
    )
  )
)
